# LOAD_SWITCH_5V.net
KiCad netlist of a schematic drawn in Altium Designer
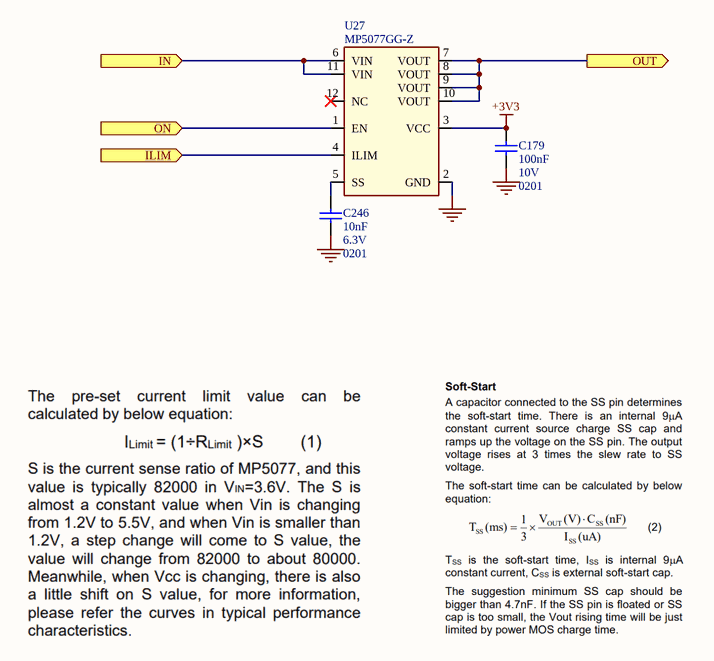
[diagram p0: LOAD_SWITCH_5V.SchDoc]

(export (version "E")
  (design (tool "Eeschema 10.0.6"))
  (components
    (comp (ref "C179")
      (value "100nF")
      (footprint "CAP-0201")
      (description "CAP CHIP 0201 100nF 10% 10V X5R")
      (fields
        (field (name "PART NUMBER") "CL03A104KP3NNNC")
        (field (name "MANUFACTURER") "Samsung Electro-Mechanics")
        (field (name "VOLTAGE") "10V")
        (field (name "CASE CODE (IMPERIAL)") "0201")
      )
      (libsource (lib "Clean") (part "CAP"))
    )
    (comp (ref "C246")
      (value "10nF")
      (footprint "CAP-0201")
      (description "CAP CHIP 0201 10nF 10% 6.3V X7R")
      (fields
        (field (name "TOLERANCE") "10%")
        (field (name "PART NUMBER") "GRM033R70J103KA01D")
        (field (name "VOLTAGE") "6.3V")
        (field (name "CASE CODE (IMPERIAL)") "0201")
      )
      (libsource (lib "Clean") (part "CAP"))
    )
    (comp (ref "U27")
      (value "MP5077GG-Z")
      (footprint "MPS QFN12 2x2mm pitch 0.4mm")
      (fields (field (name "MANUFACTURER") "MPS"))
      (libsource (lib "Clean") (part "MP5077GG-Z"))
    )
  )
  (nets
    (net (code "1") (name "+3V3") (class "Default")
      (node (ref "C179") (pin "2") (pinfunction "2_2") (pintype "passive"))
      (node (ref "U27") (pin "3") (pinfunction "VCC_3") (pintype "passive"))
    )
    (net (code "2") (name "/ILIM") (class "Default")
      (node (ref "U27") (pin "4") (pinfunction "ILIM_4") (pintype "passive"))
    )
    (net (code "3") (name "/IN") (class "Default")
      (node (ref "U27") (pin "11") (pinfunction "VIN_11") (pintype "passive"))
      (node (ref "U27") (pin "6") (pinfunction "VIN_6") (pintype "passive"))
    )
    (net (code "4") (name "/ON") (class "Default")
      (node (ref "U27") (pin "1") (pinfunction "EN_1") (pintype "passive"))
    )
    (net (code "5") (name "/OUT") (class "Default")
      (node (ref "U27") (pin "10") (pinfunction "VOUT_10") (pintype "passive"))
      (node (ref "U27") (pin "7") (pinfunction "VOUT_7") (pintype "passive"))
      (node (ref "U27") (pin "8") (pinfunction "VOUT_8") (pintype "passive"))
      (node (ref "U27") (pin "9") (pinfunction "VOUT_9") (pintype "passive"))
    )
    (net (code "6") (name "GND") (class "Default")
      (node (ref "C179") (pin "1") (pinfunction "1_1") (pintype "passive"))
      (node (ref "C246") (pin "1") (pinfunction "1_1") (pintype "passive"))
      (node (ref "U27") (pin "2") (pinfunction "GND_2") (pintype "passive"))
    )
    (net (code "7") (name "Net-(U27-SS)") (class "Default")
      (node (ref "C246") (pin "2") (pinfunction "2_2") (pintype "passive"))
      (node (ref "U27") (pin "5") (pinfunction "SS_5") (pintype "passive"))
    )
    (net (code "8") (name "unconnected-(U27-NC-Pad12)") (class "Default")
      (node (ref "U27") (pin "12") (pinfunction "NC_12") (pintype "passive+no_connect"))
    )
  )
)
